# Vent_BreakoutBord.net
KiCad netlist of a schematic drawn in EAGLE
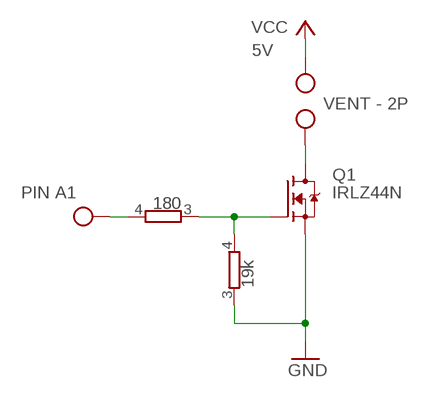
[diagram p0: schematic, sheet 1]

(export (version "E")
  (design (tool "Eeschema 10.0.6"))
  (components
    (comp (ref "Q1")
      (value "IRLZ44N")
      (footprint "eagle-import:TO254P1054X469X1930-3")
      (fields (field (name "MF") "Infineon / IR"))
      (libsource (lib "eagle-import") (part "IRLZ44N"))
    )
    (comp (ref "RN1")
      (value "19k")
      (footprint "eagle-import:SIL4")
      (libsource (lib "eagle-import") (part "E2R"))
    )
    (comp (ref "RN2")
      (value "180")
      (footprint "eagle-import:SIL4")
      (libsource (lib "eagle-import") (part "E2R"))
    )
  )
  (nets
    (net (code "1") (name "GND") (class "Default")
      (node (ref "Q1") (pin "3") (pinfunction "S_3") (pintype "passive"))
      (node (ref "RN1") (pin "3") (pinfunction "1_3") (pintype "passive"))
    )
    (net (code "2") (name "Net-(Q1-G)") (class "Default")
      (node (ref "Q1") (pin "1") (pinfunction "G_1") (pintype "passive"))
      (node (ref "RN1") (pin "4") (pinfunction "2_4") (pintype "passive"))
      (node (ref "RN2") (pin "3") (pinfunction "1_3") (pintype "passive"))
    )
    (net (code "3") (name "VCC") (class "Default")
      (node (ref "Q1") (pin "2") (pinfunction "D_2") (pintype "passive"))
      (node (ref "RN2") (pin "4") (pinfunction "2_4") (pintype "passive"))
    )
  )
)
